# pic_can_switch.net
KiCad netlist of a schematic drawn in EAGLE
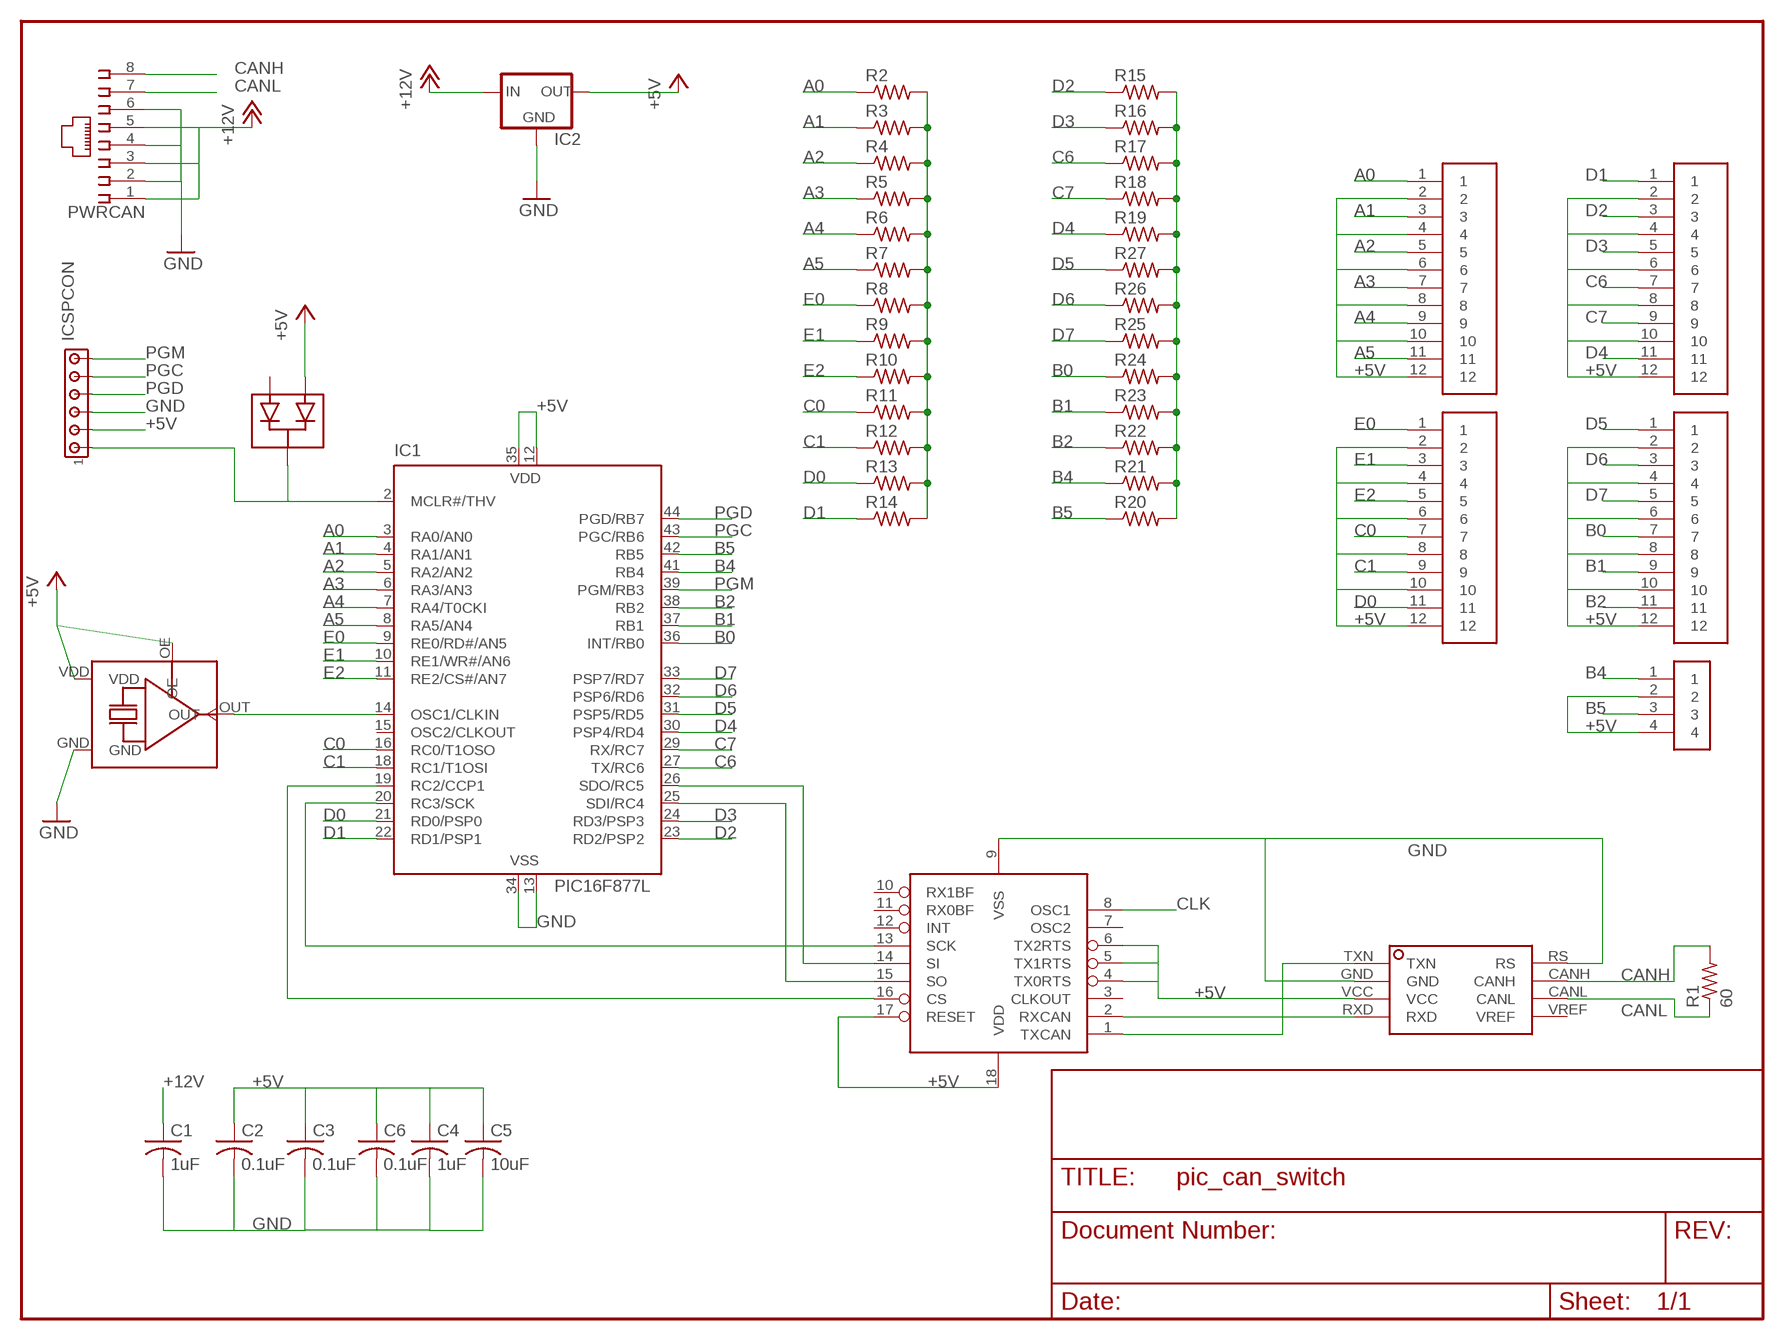
[diagram p0: schematic, sheet 1]

(export (version "E")
  (design (tool "Eeschema 10.0.6"))
  (components
    (comp (ref "C1")
      (value "1uF")
      (footprint "eagle-import:C1206")
      (libsource (lib "eagle-import") (part "C-USC1206"))
    )
    (comp (ref "C2")
      (value "0.1uF")
      (footprint "eagle-import:C0805")
      (libsource (lib "eagle-import") (part "C-USC0805"))
    )
    (comp (ref "C3")
      (value "0.1uF")
      (footprint "eagle-import:C0805")
      (libsource (lib "eagle-import") (part "C-USC0805"))
    )
    (comp (ref "C4")
      (value "1uF")
      (footprint "eagle-import:C1206")
      (libsource (lib "eagle-import") (part "C-USC1206"))
    )
    (comp (ref "C5")
      (value "10uF")
      (footprint "eagle-import:C1210")
      (libsource (lib "eagle-import") (part "C-USC1210"))
    )
    (comp (ref "C6")
      (value "0.1uF")
      (footprint "eagle-import:C0805")
      (libsource (lib "eagle-import") (part "C-USC0805"))
    )
    (comp (ref "IC1")
      (value "PIC16F877L")
      (footprint "eagle-import:PLCC-44")
      (libsource (lib "eagle-import") (part "PIC16F87L7"))
    )
    (comp (ref "IC2")
      (value "78XXL")
      (footprint "eagle-import:78XXL")
      (libsource (lib "eagle-import") (part "78XXL"))
    )
    (comp (ref "IC3")
      (value "UC5350D")
      (footprint "eagle-import:SOIC8")
      (libsource (lib "eagle-import") (part "UC5350D"))
    )
    (comp (ref "ICSPCON")
      (value "MTA06-100")
      (footprint "eagle-import:10X06MTA")
      (libsource (lib "eagle-import") (part "MTA06-100"))
    )
    (comp (ref "MCP1")
      (value "MCP2510-I/SO")
      (footprint "eagle-import:SO-18W")
      (libsource (lib "eagle-import") (part "MCP2510-I/SO"))
    )
    (comp (ref "PWRCAN")
      (value "555764-1")
      (footprint "eagle-import:555764-1")
      (libsource (lib "eagle-import") (part "555764-1"))
    )
    (comp (ref "R1")
      (value "60")
      (footprint "eagle-import:R0805")
      (libsource (lib "eagle-import") (part "R-US_R0805"))
    )
    (comp (ref "R2")
      (value "R-US_R0805")
      (footprint "eagle-import:R0805")
      (libsource (lib "eagle-import") (part "R-US_R0805"))
    )
    (comp (ref "R3")
      (value "R-US_R0805")
      (footprint "eagle-import:R0805")
      (libsource (lib "eagle-import") (part "R-US_R0805"))
    )
    (comp (ref "R4")
      (value "R-US_R0805")
      (footprint "eagle-import:R0805")
      (libsource (lib "eagle-import") (part "R-US_R0805"))
    )
    (comp (ref "R5")
      (value "R-US_R0805")
      (footprint "eagle-import:R0805")
      (libsource (lib "eagle-import") (part "R-US_R0805"))
    )
    (comp (ref "R6")
      (value "R-US_R0805")
      (footprint "eagle-import:R0805")
      (libsource (lib "eagle-import") (part "R-US_R0805"))
    )
    (comp (ref "R7")
      (value "R-US_R0805")
      (footprint "eagle-import:R0805")
      (libsource (lib "eagle-import") (part "R-US_R0805"))
    )
    (comp (ref "R8")
      (value "R-US_R0805")
      (footprint "eagle-import:R0805")
      (libsource (lib "eagle-import") (part "R-US_R0805"))
    )
    (comp (ref "R9")
      (value "R-US_R0805")
      (footprint "eagle-import:R0805")
      (libsource (lib "eagle-import") (part "R-US_R0805"))
    )
    (comp (ref "R10")
      (value "R-US_R0805")
      (footprint "eagle-import:R0805")
      (libsource (lib "eagle-import") (part "R-US_R0805"))
    )
    (comp (ref "R11")
      (value "R-US_R0805")
      (footprint "eagle-import:R0805")
      (libsource (lib "eagle-import") (part "R-US_R0805"))
    )
    (comp (ref "R12")
      (value "R-US_R0805")
      (footprint "eagle-import:R0805")
      (libsource (lib "eagle-import") (part "R-US_R0805"))
    )
    (comp (ref "R13")
      (value "R-US_R0805")
      (footprint "eagle-import:R0805")
      (libsource (lib "eagle-import") (part "R-US_R0805"))
    )
    (comp (ref "R14")
      (value "R-US_R0805")
      (footprint "eagle-import:R0805")
      (libsource (lib "eagle-import") (part "R-US_R0805"))
    )
    (comp (ref "R15")
      (value "R-US_R0805")
      (footprint "eagle-import:R0805")
      (libsource (lib "eagle-import") (part "R-US_R0805"))
    )
    (comp (ref "R16")
      (value "R-US_R0805")
      (footprint "eagle-import:R0805")
      (libsource (lib "eagle-import") (part "R-US_R0805"))
    )
    (comp (ref "R17")
      (value "R-US_R0805")
      (footprint "eagle-import:R0805")
      (libsource (lib "eagle-import") (part "R-US_R0805"))
    )
    (comp (ref "R18")
      (value "R-US_R0805")
      (footprint "eagle-import:R0805")
      (libsource (lib "eagle-import") (part "R-US_R0805"))
    )
    (comp (ref "R19")
      (value "R-US_R0805")
      (footprint "eagle-import:R0805")
      (libsource (lib "eagle-import") (part "R-US_R0805"))
    )
    (comp (ref "R20")
      (value "R-US_R0805")
      (footprint "eagle-import:R0805")
      (libsource (lib "eagle-import") (part "R-US_R0805"))
    )
    (comp (ref "R21")
      (value "R-US_R0805")
      (footprint "eagle-import:R0805")
      (libsource (lib "eagle-import") (part "R-US_R0805"))
    )
    (comp (ref "R22")
      (value "R-US_R0805")
      (footprint "eagle-import:R0805")
      (libsource (lib "eagle-import") (part "R-US_R0805"))
    )
    (comp (ref "R23")
      (value "R-US_R0805")
      (footprint "eagle-import:R0805")
      (libsource (lib "eagle-import") (part "R-US_R0805"))
    )
    (comp (ref "R24")
      (value "R-US_R0805")
      (footprint "eagle-import:R0805")
      (libsource (lib "eagle-import") (part "R-US_R0805"))
    )
    (comp (ref "R25")
      (value "R-US_R0805")
      (footprint "eagle-import:R0805")
      (libsource (lib "eagle-import") (part "R-US_R0805"))
    )
    (comp (ref "R26")
      (value "R-US_R0805")
      (footprint "eagle-import:R0805")
      (libsource (lib "eagle-import") (part "R-US_R0805"))
    )
    (comp (ref "R27")
      (value "R-US_R0805")
      (footprint "eagle-import:R0805")
      (libsource (lib "eagle-import") (part "R-US_R0805"))
    )
    (comp (ref "TB1")
      (value "MPT0.5/12-2.54")
      (footprint "eagle-import:MPT0.5_12-2.54")
      (libsource (lib "eagle-import") (part "MPT0.5/12-2.54"))
    )
    (comp (ref "TB2")
      (value "MPT0.5/12-2.54")
      (footprint "eagle-import:MPT0.5_12-2.54")
      (libsource (lib "eagle-import") (part "MPT0.5/12-2.54"))
    )
    (comp (ref "TB3")
      (value "MPT0.5/12-2.54")
      (footprint "eagle-import:MPT0.5_12-2.54")
      (libsource (lib "eagle-import") (part "MPT0.5/12-2.54"))
    )
    (comp (ref "TB4")
      (value "MPT0.5/12-2.54")
      (footprint "eagle-import:MPT0.5_12-2.54")
      (libsource (lib "eagle-import") (part "MPT0.5/12-2.54"))
    )
    (comp (ref "TB5")
      (value "MPT0.5/4-2.54\"")
      (footprint "eagle-import:MPT0.5_4-2.54")
      (libsource (lib "eagle-import") (part "MPT0.5/4-2.54{dblquote}"))
    )
    (comp (ref "U$1")
      (value "SG-615P")
      (footprint "eagle-import:SG-615")
      (libsource (lib "eagle-import") (part "SG-615P"))
    )
    (comp (ref "U$2")
      (value "BAV70_")
      (footprint "eagle-import:SOT-23")
      (libsource (lib "eagle-import") (part "BAV70_"))
    )
  )
  (nets
    (net (code "1") (name "+5V") (class "Default")
      (node (ref "C2") (pin "1") (pinfunction "1_1") (pintype "passive"))
      (node (ref "C3") (pin "1") (pinfunction "1_1") (pintype "passive"))
      (node (ref "C4") (pin "1") (pinfunction "1_1") (pintype "passive"))
      (node (ref "C5") (pin "1") (pinfunction "1_1") (pintype "passive"))
      (node (ref "C6") (pin "1") (pinfunction "1_1") (pintype "passive"))
      (node (ref "IC1") (pin "12") (pinfunction "VDD_12") (pintype "power_in"))
      (node (ref "IC1") (pin "35") (pinfunction "VDD_35") (pintype "power_in"))
      (node (ref "IC2") (pin "OUT") (pinfunction "OUT_OUT") (pintype "passive"))
      (node (ref "IC3") (pin "VCC") (pinfunction "VCC_VCC") (pintype "bidirectional"))
      (node (ref "ICSPCON") (pin "5") (pinfunction "2_5") (pintype "passive"))
      (node (ref "MCP1") (pin "17") (pinfunction "RESET_17") (pintype "input"))
      (node (ref "MCP1") (pin "18") (pinfunction "VDD_18") (pintype "power_in"))
      (node (ref "MCP1") (pin "4") (pinfunction "TX0RTS_4") (pintype "input"))
      (node (ref "MCP1") (pin "5") (pinfunction "TX1RTS_5") (pintype "input"))
      (node (ref "MCP1") (pin "6") (pinfunction "TX2RTS_6") (pintype "input"))
      (node (ref "TB1") (pin "10") (pinfunction "10_10") (pintype "bidirectional"))
      (node (ref "TB1") (pin "12") (pinfunction "12_12") (pintype "bidirectional"))
      (node (ref "TB1") (pin "2") (pinfunction "2_2") (pintype "bidirectional"))
      (node (ref "TB1") (pin "4") (pinfunction "4_4") (pintype "bidirectional"))
      (node (ref "TB1") (pin "6") (pinfunction "6_6") (pintype "bidirectional"))
      (node (ref "TB1") (pin "8") (pinfunction "8_8") (pintype "bidirectional"))
      (node (ref "TB2") (pin "10") (pinfunction "10_10") (pintype "bidirectional"))
      (node (ref "TB2") (pin "12") (pinfunction "12_12") (pintype "bidirectional"))
      (node (ref "TB2") (pin "2") (pinfunction "2_2") (pintype "bidirectional"))
      (node (ref "TB2") (pin "4") (pinfunction "4_4") (pintype "bidirectional"))
      (node (ref "TB2") (pin "6") (pinfunction "6_6") (pintype "bidirectional"))
      (node (ref "TB2") (pin "8") (pinfunction "8_8") (pintype "bidirectional"))
      (node (ref "TB3") (pin "10") (pinfunction "10_10") (pintype "bidirectional"))
      (node (ref "TB3") (pin "12") (pinfunction "12_12") (pintype "bidirectional"))
      (node (ref "TB3") (pin "2") (pinfunction "2_2") (pintype "bidirectional"))
      (node (ref "TB3") (pin "4") (pinfunction "4_4") (pintype "bidirectional"))
      (node (ref "TB3") (pin "6") (pinfunction "6_6") (pintype "bidirectional"))
      (node (ref "TB3") (pin "8") (pinfunction "8_8") (pintype "bidirectional"))
      (node (ref "TB4") (pin "10") (pinfunction "10_10") (pintype "bidirectional"))
      (node (ref "TB4") (pin "12") (pinfunction "12_12") (pintype "bidirectional"))
      (node (ref "TB4") (pin "2") (pinfunction "2_2") (pintype "bidirectional"))
      (node (ref "TB4") (pin "4") (pinfunction "4_4") (pintype "bidirectional"))
      (node (ref "TB4") (pin "6") (pinfunction "6_6") (pintype "bidirectional"))
      (node (ref "TB4") (pin "8") (pinfunction "8_8") (pintype "bidirectional"))
      (node (ref "TB5") (pin "2") (pinfunction "2_2") (pintype "bidirectional"))
      (node (ref "TB5") (pin "4") (pinfunction "4_4") (pintype "bidirectional"))
      (node (ref "U$1") (pin "OE") (pinfunction "OE_OE") (pintype "input"))
      (node (ref "U$1") (pin "VDD") (pinfunction "VDD_VDD") (pintype "power_in"))
      (node (ref "U$2") (pin "1") (pinfunction "A1_1") (pintype "bidirectional"))
    )
    (net (code "2") (name "+12V") (class "Default")
      (node (ref "C1") (pin "1") (pinfunction "1_1") (pintype "passive"))
      (node (ref "IC2") (pin "IN") (pinfunction "IN_IN") (pintype "input"))
      (node (ref "PWRCAN") (pin "1") (pinfunction "1_1") (pintype "passive"))
      (node (ref "PWRCAN") (pin "3") (pinfunction "3_3") (pintype "passive"))
      (node (ref "PWRCAN") (pin "5") (pinfunction "5_5") (pintype "passive"))
    )
    (net (code "3") (name "/A0") (class "Default")
      (node (ref "IC1") (pin "3") (pinfunction "RA0/AN0_3") (pintype "bidirectional"))
      (node (ref "R2") (pin "1") (pinfunction "1_1") (pintype "passive"))
      (node (ref "TB1") (pin "1") (pinfunction "1_1") (pintype "bidirectional"))
    )
    (net (code "4") (name "/A1") (class "Default")
      (node (ref "IC1") (pin "4") (pinfunction "RA1/AN1_4") (pintype "bidirectional"))
      (node (ref "R3") (pin "1") (pinfunction "1_1") (pintype "passive"))
      (node (ref "TB1") (pin "3") (pinfunction "3_3") (pintype "bidirectional"))
    )
    (net (code "5") (name "/A2") (class "Default")
      (node (ref "IC1") (pin "5") (pinfunction "RA2/AN2_5") (pintype "bidirectional"))
      (node (ref "R4") (pin "1") (pinfunction "1_1") (pintype "passive"))
      (node (ref "TB1") (pin "5") (pinfunction "5_5") (pintype "bidirectional"))
    )
    (net (code "6") (name "/A3") (class "Default")
      (node (ref "IC1") (pin "6") (pinfunction "RA3/AN3_6") (pintype "bidirectional"))
      (node (ref "R5") (pin "1") (pinfunction "1_1") (pintype "passive"))
      (node (ref "TB1") (pin "7") (pinfunction "7_7") (pintype "bidirectional"))
    )
    (net (code "7") (name "/A4") (class "Default")
      (node (ref "IC1") (pin "7") (pinfunction "RA4/T0CKI_7") (pintype "bidirectional"))
      (node (ref "R6") (pin "1") (pinfunction "1_1") (pintype "passive"))
      (node (ref "TB1") (pin "9") (pinfunction "9_9") (pintype "bidirectional"))
    )
    (net (code "8") (name "/A5") (class "Default")
      (node (ref "IC1") (pin "8") (pinfunction "RA5/AN4_8") (pintype "bidirectional"))
      (node (ref "R7") (pin "1") (pinfunction "1_1") (pintype "passive"))
      (node (ref "TB1") (pin "11") (pinfunction "11_11") (pintype "bidirectional"))
    )
    (net (code "9") (name "/B0") (class "Default")
      (node (ref "IC1") (pin "36") (pinfunction "INT/RB0_36") (pintype "bidirectional"))
      (node (ref "R24") (pin "1") (pinfunction "1_1") (pintype "passive"))
      (node (ref "TB4") (pin "7") (pinfunction "7_7") (pintype "bidirectional"))
    )
    (net (code "10") (name "/B1") (class "Default")
      (node (ref "IC1") (pin "37") (pinfunction "RB1_37") (pintype "bidirectional"))
      (node (ref "R23") (pin "1") (pinfunction "1_1") (pintype "passive"))
      (node (ref "TB4") (pin "9") (pinfunction "9_9") (pintype "bidirectional"))
    )
    (net (code "11") (name "/B2") (class "Default")
      (node (ref "IC1") (pin "38") (pinfunction "RB2_38") (pintype "bidirectional"))
      (node (ref "R22") (pin "1") (pinfunction "1_1") (pintype "passive"))
      (node (ref "TB4") (pin "11") (pinfunction "11_11") (pintype "bidirectional"))
    )
    (net (code "12") (name "/B4") (class "Default")
      (node (ref "IC1") (pin "41") (pinfunction "RB4_41") (pintype "bidirectional"))
      (node (ref "R21") (pin "1") (pinfunction "1_1") (pintype "passive"))
      (node (ref "TB5") (pin "1") (pinfunction "1_1") (pintype "bidirectional"))
    )
    (net (code "13") (name "/B5") (class "Default")
      (node (ref "IC1") (pin "42") (pinfunction "RB5_42") (pintype "bidirectional"))
      (node (ref "R20") (pin "1") (pinfunction "1_1") (pintype "passive"))
      (node (ref "TB5") (pin "3") (pinfunction "3_3") (pintype "bidirectional"))
    )
    (net (code "14") (name "/C0") (class "Default")
      (node (ref "IC1") (pin "16") (pinfunction "RC0/T1OSO_16") (pintype "bidirectional"))
      (node (ref "R11") (pin "1") (pinfunction "1_1") (pintype "passive"))
      (node (ref "TB2") (pin "7") (pinfunction "7_7") (pintype "bidirectional"))
    )
    (net (code "15") (name "/C1") (class "Default")
      (node (ref "IC1") (pin "18") (pinfunction "RC1/T1OSI_18") (pintype "bidirectional"))
      (node (ref "R12") (pin "1") (pinfunction "1_1") (pintype "passive"))
      (node (ref "TB2") (pin "9") (pinfunction "9_9") (pintype "bidirectional"))
    )
    (net (code "16") (name "/C6") (class "Default")
      (node (ref "IC1") (pin "27") (pinfunction "TX/RC6_27") (pintype "bidirectional"))
      (node (ref "R17") (pin "1") (pinfunction "1_1") (pintype "passive"))
      (node (ref "TB3") (pin "7") (pinfunction "7_7") (pintype "bidirectional"))
    )
    (net (code "17") (name "/C7") (class "Default")
      (node (ref "IC1") (pin "29") (pinfunction "RX/RC7_29") (pintype "bidirectional"))
      (node (ref "R18") (pin "1") (pinfunction "1_1") (pintype "passive"))
      (node (ref "TB3") (pin "9") (pinfunction "9_9") (pintype "bidirectional"))
    )
    (net (code "18") (name "/CANH") (class "Default")
      (node (ref "IC3") (pin "CANH") (pinfunction "CANH_CANH") (pintype "bidirectional"))
      (node (ref "PWRCAN") (pin "8") (pinfunction "8_8") (pintype "passive"))
      (node (ref "R1") (pin "2") (pinfunction "2_2") (pintype "passive"))
    )
    (net (code "19") (name "/CANL") (class "Default")
      (node (ref "IC3") (pin "CANL") (pinfunction "CANL_CANL") (pintype "bidirectional"))
      (node (ref "PWRCAN") (pin "7") (pinfunction "7_7") (pintype "passive"))
      (node (ref "R1") (pin "1") (pinfunction "1_1") (pintype "passive"))
    )
    (net (code "20") (name "/CLK") (class "Default")
      (node (ref "IC1") (pin "14") (pinfunction "OSC1/CLKIN_14") (pintype "input"))
      (node (ref "MCP1") (pin "8") (pinfunction "OSC1_8") (pintype "input"))
      (node (ref "U$1") (pin "OUT") (pinfunction "OUT_OUT") (pintype "bidirectional"))
    )
    (net (code "21") (name "/D0") (class "Default")
      (node (ref "IC1") (pin "21") (pinfunction "RD0/PSP0_21") (pintype "bidirectional"))
      (node (ref "R13") (pin "1") (pinfunction "1_1") (pintype "passive"))
      (node (ref "TB2") (pin "11") (pinfunction "11_11") (pintype "bidirectional"))
    )
    (net (code "22") (name "/D1") (class "Default")
      (node (ref "IC1") (pin "22") (pinfunction "RD1/PSP1_22") (pintype "bidirectional"))
      (node (ref "R14") (pin "1") (pinfunction "1_1") (pintype "passive"))
      (node (ref "TB3") (pin "1") (pinfunction "1_1") (pintype "bidirectional"))
    )
    (net (code "23") (name "/D2") (class "Default")
      (node (ref "IC1") (pin "23") (pinfunction "RD2/PSP2_23") (pintype "bidirectional"))
      (node (ref "R15") (pin "1") (pinfunction "1_1") (pintype "passive"))
      (node (ref "TB3") (pin "3") (pinfunction "3_3") (pintype "bidirectional"))
    )
    (net (code "24") (name "/D3") (class "Default")
      (node (ref "IC1") (pin "24") (pinfunction "RD3/PSP3_24") (pintype "bidirectional"))
      (node (ref "R16") (pin "1") (pinfunction "1_1") (pintype "passive"))
      (node (ref "TB3") (pin "5") (pinfunction "5_5") (pintype "bidirectional"))
    )
    (net (code "25") (name "/D4") (class "Default")
      (node (ref "IC1") (pin "30") (pinfunction "PSP4/RD4_30") (pintype "bidirectional"))
      (node (ref "R19") (pin "1") (pinfunction "1_1") (pintype "passive"))
      (node (ref "TB3") (pin "11") (pinfunction "11_11") (pintype "bidirectional"))
    )
    (net (code "26") (name "/D5") (class "Default")
      (node (ref "IC1") (pin "31") (pinfunction "PSP5/RD5_31") (pintype "bidirectional"))
      (node (ref "R27") (pin "1") (pinfunction "1_1") (pintype "passive"))
      (node (ref "TB4") (pin "1") (pinfunction "1_1") (pintype "bidirectional"))
    )
    (net (code "27") (name "/D6") (class "Default")
      (node (ref "IC1") (pin "32") (pinfunction "PSP6/RD6_32") (pintype "bidirectional"))
      (node (ref "R26") (pin "1") (pinfunction "1_1") (pintype "passive"))
      (node (ref "TB4") (pin "3") (pinfunction "3_3") (pintype "bidirectional"))
    )
    (net (code "28") (name "/D7") (class "Default")
      (node (ref "IC1") (pin "33") (pinfunction "PSP7/RD7_33") (pintype "bidirectional"))
      (node (ref "R25") (pin "1") (pinfunction "1_1") (pintype "passive"))
      (node (ref "TB4") (pin "5") (pinfunction "5_5") (pintype "bidirectional"))
    )
    (net (code "29") (name "/E0") (class "Default")
      (node (ref "IC1") (pin "9") (pinfunction "RE0/RD#/AN5_9") (pintype "bidirectional"))
      (node (ref "R8") (pin "1") (pinfunction "1_1") (pintype "passive"))
      (node (ref "TB2") (pin "1") (pinfunction "1_1") (pintype "bidirectional"))
    )
    (net (code "30") (name "/E1") (class "Default")
      (node (ref "IC1") (pin "10") (pinfunction "RE1/WR#/AN6_10") (pintype "bidirectional"))
      (node (ref "R9") (pin "1") (pinfunction "1_1") (pintype "passive"))
      (node (ref "TB2") (pin "3") (pinfunction "3_3") (pintype "bidirectional"))
    )
    (net (code "31") (name "/E2") (class "Default")
      (node (ref "IC1") (pin "11") (pinfunction "RE2/CS#/AN7_11") (pintype "bidirectional"))
      (node (ref "R10") (pin "1") (pinfunction "1_1") (pintype "passive"))
      (node (ref "TB2") (pin "5") (pinfunction "5_5") (pintype "bidirectional"))
    )
    (net (code "32") (name "/PGC") (class "Default")
      (node (ref "IC1") (pin "43") (pinfunction "PGC/RB6_43") (pintype "bidirectional"))
      (node (ref "ICSPCON") (pin "2") (pinfunction "5_2") (pintype "passive"))
    )
    (net (code "33") (name "/PGD") (class "Default")
      (node (ref "IC1") (pin "44") (pinfunction "PGD/RB7_44") (pintype "bidirectional"))
      (node (ref "ICSPCON") (pin "3") (pinfunction "4_3") (pintype "passive"))
    )
    (net (code "34") (name "/PGM") (class "Default")
      (node (ref "IC1") (pin "39") (pinfunction "PGM/RB3_39") (pintype "bidirectional"))
      (node (ref "ICSPCON") (pin "1") (pinfunction "6_1") (pintype "passive"))
    )
    (net (code "35") (name "GND") (class "Default")
      (node (ref "C1") (pin "2") (pinfunction "2_2") (pintype "passive"))
      (node (ref "C2") (pin "2") (pinfunction "2_2") (pintype "passive"))
      (node (ref "C3") (pin "2") (pinfunction "2_2") (pintype "passive"))
      (node (ref "C4") (pin "2") (pinfunction "2_2") (pintype "passive"))
      (node (ref "C5") (pin "2") (pinfunction "2_2") (pintype "passive"))
      (node (ref "C6") (pin "2") (pinfunction "2_2") (pintype "passive"))
      (node (ref "IC1") (pin "13") (pinfunction "VSS_13") (pintype "power_in"))
      (node (ref "IC1") (pin "34") (pinfunction "VSS_34") (pintype "power_in"))
      (node (ref "IC2") (pin "GND") (pinfunction "GND_GND") (pintype "input"))
      (node (ref "IC3") (pin "GND") (pinfunction "GND_GND") (pintype "bidirectional"))
      (node (ref "IC3") (pin "RS") (pinfunction "RS_RS") (pintype "bidirectional"))
      (node (ref "ICSPCON") (pin "4") (pinfunction "3_4") (pintype "passive"))
      (node (ref "MCP1") (pin "9") (pinfunction "VSS_9") (pintype "power_in"))
      (node (ref "PWRCAN") (pin "2") (pinfunction "2_2") (pintype "passive"))
      (node (ref "PWRCAN") (pin "4") (pinfunction "4_4") (pintype "passive"))
      (node (ref "PWRCAN") (pin "6") (pinfunction "6_6") (pintype "passive"))
      (node (ref "R10") (pin "2") (pinfunction "2_2") (pintype "passive"))
      (node (ref "R11") (pin "2") (pinfunction "2_2") (pintype "passive"))
      (node (ref "R12") (pin "2") (pinfunction "2_2") (pintype "passive"))
      (node (ref "R13") (pin "2") (pinfunction "2_2") (pintype "passive"))
      (node (ref "R14") (pin "2") (pinfunction "2_2") (pintype "passive"))
      (node (ref "R15") (pin "2") (pinfunction "2_2") (pintype "passive"))
      (node (ref "R16") (pin "2") (pinfunction "2_2") (pintype "passive"))
      (node (ref "R17") (pin "2") (pinfunction "2_2") (pintype "passive"))
      (node (ref "R18") (pin "2") (pinfunction "2_2") (pintype "passive"))
      (node (ref "R19") (pin "2") (pinfunction "2_2") (pintype "passive"))
      (node (ref "R2") (pin "2") (pinfunction "2_2") (pintype "passive"))
      (node (ref "R20") (pin "2") (pinfunction "2_2") (pintype "passive"))
      (node (ref "R21") (pin "2") (pinfunction "2_2") (pintype "passive"))
      (node (ref "R22") (pin "2") (pinfunction "2_2") (pintype "passive"))
      (node (ref "R23") (pin "2") (pinfunction "2_2") (pintype "passive"))
      (node (ref "R24") (pin "2") (pinfunction "2_2") (pintype "passive"))
      (node (ref "R25") (pin "2") (pinfunction "2_2") (pintype "passive"))
      (node (ref "R26") (pin "2") (pinfunction "2_2") (pintype "passive"))
      (node (ref "R27") (pin "2") (pinfunction "2_2") (pintype "passive"))
      (node (ref "R3") (pin "2") (pinfunction "2_2") (pintype "passive"))
      (node (ref "R4") (pin "2") (pinfunction "2_2") (pintype "passive"))
      (node (ref "R5") (pin "2") (pinfunction "2_2") (pintype "passive"))
      (node (ref "R6") (pin "2") (pinfunction "2_2") (pintype "passive"))
      (node (ref "R7") (pin "2") (pinfunction "2_2") (pintype "passive"))
      (node (ref "R8") (pin "2") (pinfunction "2_2") (pintype "passive"))
      (node (ref "R9") (pin "2") (pinfunction "2_2") (pintype "passive"))
      (node (ref "U$1") (pin "GND") (pinfunction "GND_GND") (pintype "power_in"))
    )
    (net (code "36") (name "Net-(IC1-MCLR#{slash}THV)") (class "Default")
      (node (ref "IC1") (pin "2") (pinfunction "MCLR#/THV_2") (pintype "input"))
      (node (ref "ICSPCON") (pin "6") (pinfunction "1_6") (pintype "passive"))
      (node (ref "U$2") (pin "3") (pinfunction "C_3") (pintype "bidirectional"))
    )
    (net (code "37") (name "Net-(IC1-RC2{slash}CCP1)") (class "Default")
      (node (ref "IC1") (pin "19") (pinfunction "RC2/CCP1_19") (pintype "bidirectional"))
      (node (ref "MCP1") (pin "16") (pinfunction "CS_16") (pintype "input"))
    )
    (net (code "38") (name "Net-(IC1-RC3{slash}SCK)") (class "Default")
      (node (ref "IC1") (pin "20") (pinfunction "RC3/SCK_20") (pintype "bidirectional"))
      (node (ref "MCP1") (pin "13") (pinfunction "SCK_13") (pintype "input"))
    )
    (net (code "39") (name "Net-(IC1-SDI{slash}RC4)") (class "Default")
      (node (ref "IC1") (pin "25") (pinfunction "SDI/RC4_25") (pintype "bidirectional"))
      (node (ref "MCP1") (pin "15") (pinfunction "SO_15") (pintype "output"))
    )
    (net (code "40") (name "Net-(IC1-SDO{slash}RC5)") (class "Default")
      (node (ref "IC1") (pin "26") (pinfunction "SDO/RC5_26") (pintype "bidirectional"))
      (node (ref "MCP1") (pin "14") (pinfunction "SI_14") (pintype "input"))
    )
    (net (code "41") (name "Net-(MCP1-RXCAN)") (class "Default")
      (node (ref "IC3") (pin "RXD") (pinfunction "RXD_RXD") (pintype "bidirectional"))
      (node (ref "MCP1") (pin "2") (pinfunction "RXCAN_2") (pintype "input"))
    )
    (net (code "42") (name "Net-(MCP1-TXCAN)") (class "Default")
      (node (ref "IC3") (pin "TXN") (pinfunction "TXN_TXN") (pintype "bidirectional"))
      (node (ref "MCP1") (pin "1") (pinfunction "TXCAN_1") (pintype "output"))
    )
    (net (code "43") (name "unconnected-(IC1-OSC2{slash}CLKOUT-Pad15)") (class "Default")
      (node (ref "IC1") (pin "15") (pinfunction "OSC2/CLKOUT_15") (pintype "output"))
    )
    (net (code "44") (name "unconnected-(IC3-PadVREF)") (class "Default")
      (node (ref "IC3") (pin "VREF") (pinfunction "VREF_VREF") (pintype "bidirectional"))
    )
    (net (code "45") (name "unconnected-(MCP1-CLKOUT-Pad3)") (class "Default")
      (node (ref "MCP1") (pin "3") (pinfunction "CLKOUT_3") (pintype "output"))
    )
    (net (code "46") (name "unconnected-(MCP1-INT-Pad12)") (class "Default")
      (node (ref "MCP1") (pin "12") (pinfunction "INT_12") (pintype "output"))
    )
    (net (code "47") (name "unconnected-(MCP1-OSC2-Pad7)") (class "Default")
      (node (ref "MCP1") (pin "7") (pinfunction "OSC2_7") (pintype "output"))
    )
    (net (code "48") (name "unconnected-(MCP1-RX0BF-Pad11)") (class "Default")
      (node (ref "MCP1") (pin "11") (pinfunction "RX0BF_11") (pintype "output"))
    )
    (net (code "49") (name "unconnected-(MCP1-RX1BF-Pad10)") (class "Default")
      (node (ref "MCP1") (pin "10") (pinfunction "RX1BF_10") (pintype "output"))
    )
    (net (code "50") (name "unconnected-(U$2-A2-Pad2)") (class "Default")
      (node (ref "U$2") (pin "2") (pinfunction "A2_2") (pintype "bidirectional"))
    )
  )
)
